# POWER.net
KiCad netlist of a schematic drawn in Altium Designer
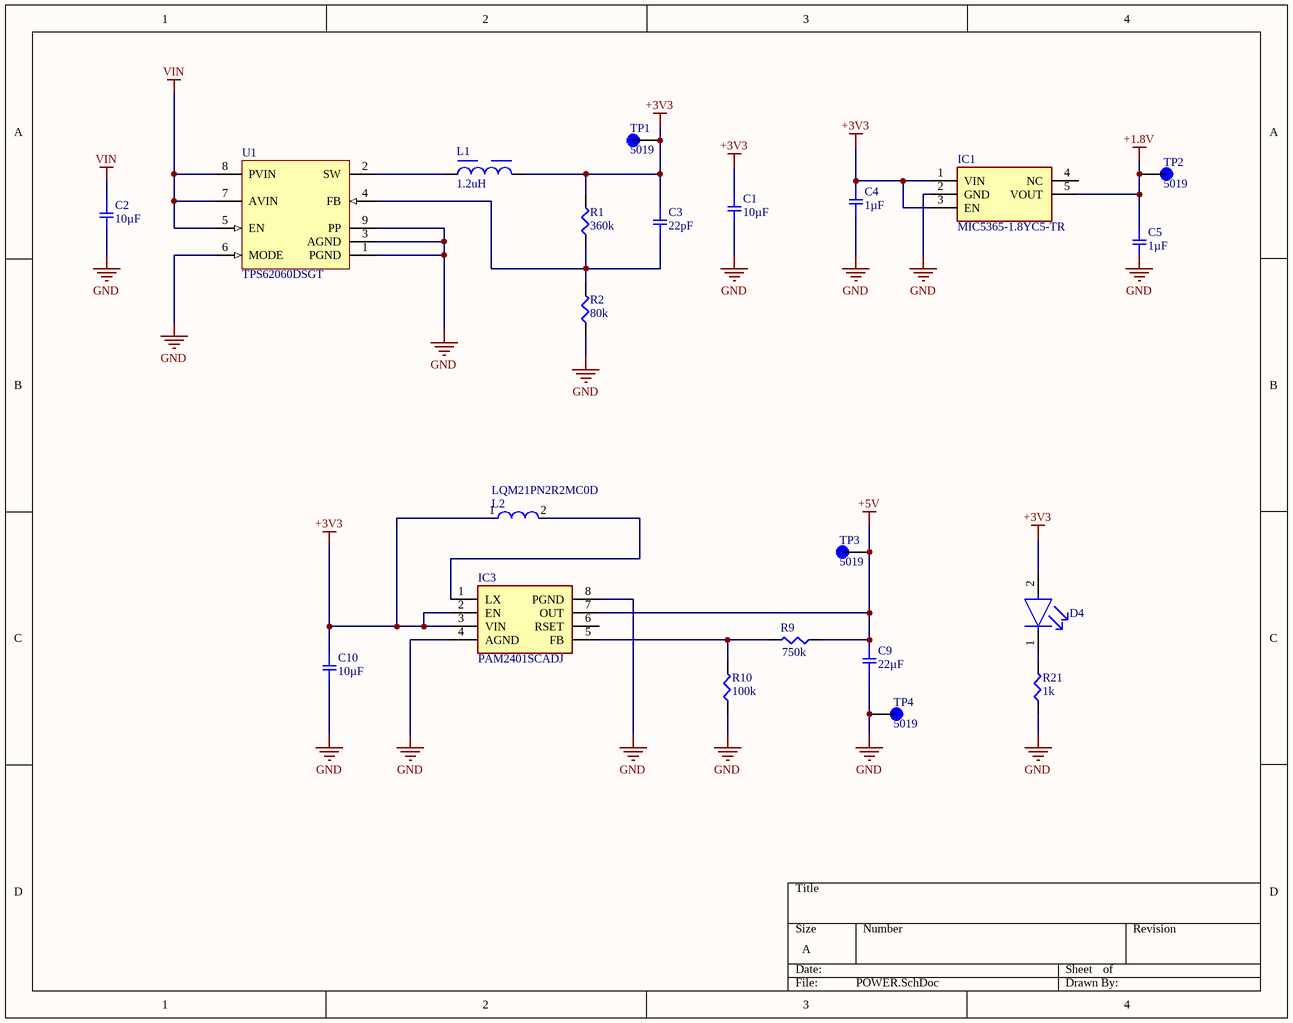
[diagram p0: POWER.SchDoc]

(export (version "E")
  (design (tool "Eeschema 10.0.6"))
  (components
    (comp (ref "C1")
      (value "10µF")
      (footprint "SMD-0603C")
      (description "CAP CER 10UF 16V X6S 0603")
      (fields
        (field (name "DIGI-KEY PART NUMBER") "490-7198-1-ND")
        (field (name "PART NUMBER") "GRM188C81C106MA73D")
      )
      (libsource (lib "capacitor_murata_0603") (part "GRM188C81C106MA73D"))
    )
    (comp (ref "C2")
      (value "10µF")
      (footprint "SMD-0603C")
      (description "CAP CER 10UF 16V X6S 0603")
      (fields
        (field (name "DIGI-KEY PART NUMBER") "490-7198-1-ND")
        (field (name "PART NUMBER") "GRM188C81C106MA73D")
      )
      (libsource (lib "capacitor_murata_0603") (part "GRM188C81C106MA73D"))
    )
    (comp (ref "C3")
      (value "22pF")
      (footprint "SMD-0402C")
      (description "CAP CER 22PF 50V NP0 0402")
      (fields
        (field (name "DIGI-KEY PART NUMBER") "490-9648-1-ND")
        (field (name "PART NUMBER") "GCM1555C1H220JA16D")
      )
      (libsource (lib "capacitor_murata_0402") (part "GCM1555C1H220JA16D"))
    )
    (comp (ref "C4")
      (value "1µF")
      (footprint "SMD-0402C")
      (description "CAP CER 1UF 10V X7S 0402")
      (fields
        (field (name "DIGI-KEY PART NUMBER") "490-13409-1-ND")
        (field (name "PART NUMBER") "GCM155C71A105KE38D")
      )
      (libsource (lib "capacitor_murata_0402") (part "GCM155C71A105KE38D"))
    )
    (comp (ref "C5")
      (value "1µF")
      (footprint "SMD-0402C")
      (description "CAP CER 1UF 10V X7S 0402")
      (fields
        (field (name "DIGI-KEY PART NUMBER") "490-13409-1-ND")
        (field (name "PART NUMBER") "GCM155C71A105KE38D")
      )
      (libsource (lib "capacitor_murata_0402") (part "GCM155C71A105KE38D"))
    )
    (comp (ref "C9")
      (value "22µF")
      (footprint "SMD-0603C")
      (description "CAP CER 22UF 6.3V X5S 0603")
      (fields
        (field (name "DIGI-KEY PART NUMBER") "490-10468-1-ND")
        (field (name "PART NUMBER") "GRM188C60J226MEA0D")
      )
      (libsource (lib "capacitor_murata_0603") (part "GRM188C60J226MEA0D"))
    )
    (comp (ref "C10")
      (value "10µF")
      (footprint "SMD-0603C")
      (description "CAP CER 10UF 16V X6S 0603")
      (fields
        (field (name "DIGI-KEY PART NUMBER") "490-7198-1-ND")
        (field (name "PART NUMBER") "GRM188C81C106MA73D")
      )
      (libsource (lib "capacitor_murata_0603") (part "GRM188C81C106MA73D"))
    )
    (comp (ref "D4")
      (value "APHHS1005CGCK")
      (footprint "FP-APHHS1005CGCK-MFG")
      (description "LED GREEN CLEAR CHIP SMD")
      (libsource (lib "Altium Content Vault") (part "8706943c75ba83719d021d2fdc84c58"))
    )
    (comp (ref "IC1")
      (value "MIC5365-1.8YC5-TR")
      (footprint "SamacSys:SOT65P210X110-5N")
      (description "Integrated Circuit")
      (fields (field (name "MOUSER PART NUMBER") "998-MIC5365-1.8YC5TR"))
      (libsource (lib "SamacSys") (part "MIC5365-1.8YC5-TR"))
    )
    (comp (ref "IC3")
      (value "PAM2401SCADJ")
      (footprint "SamacSys:SOP65P490X110-8N")
      (description "Integrated Circuit")
      (fields (field (name "MOUSER PART NUMBER") "621-PAM2401SCADJ"))
      (libsource (lib "*") (part "PAM2401SCADJ"))
    )
    (comp (ref "L1")
      (value "1.2uH")
      (footprint "WE-MAIA_1610")
      (description "78438313012 Power Inductor, Aec-Q200, 1.2Uh, 1.3A Rohs Compliant: Yes")
      (libsource (lib "Altium Content Vault") (part "Inductor - 3"))
    )
    (comp (ref "L2")
      (value "LQM21PN2R2MC0D")
      (footprint "FP-LQM21PN_C0-IPC_A")
      (description "Multilayer Type Inductor for Power Lines, 0805 (2012), 2.2μH, 20%, 0.425Ω, 0.6A")
      (fields (field (name "TOLERANCE") "20%"))
      (libsource (lib "Altium Content Vault") (part "725321dda6339637d4d059423bc1c3c"))
    )
    (comp (ref "R1")
      (value "360k")
      (footprint "SMD-0402-RES")
      (description "RES SMD 360K OHM 5% 1/10W 0402")
      (fields (field (name "PART NUMBER") "ERJ-2GEJ364X") (field (name "DIGI-KEY PART NUMBER") "P360KJCT-ND"))
      (libsource (lib "Panasonic_ERJ_0402") (part "ERJ-2GEJ364X"))
    )
    (comp (ref "R2")
      (value "80k")
      (footprint "SMD-0402-RES")
      (description "RES SMD 360K OHM 5% 1/10W 0402")
      (fields (field (name "PART NUMBER") "ERJ-2GEJ364X") (field (name "DIGI-KEY PART NUMBER") "P360KJCT-ND"))
      (libsource (lib "Panasonic_ERJ_0402") (part "ERJ-2GEJ364X"))
    )
    (comp (ref "R9")
      (value "750k")
      (footprint "SMD-0402-RES")
      (description "RES SMD 750K OHM 1% 1/10W 0402")
      (fields
        (field (name "PART NUMBER") "ERJ-2RKF7503X")
        (field (name "DIGI-KEY PART NUMBER") "P750KLCT-ND")
      )
      (libsource (lib "Panasonic_ERJ_0402") (part "ERJ-2RKF7503X"))
    )
    (comp (ref "R10")
      (value "100k")
      (footprint "SMD-0402-RES")
      (description "RES SMD 100K OHM 5% 1/10W 0402")
      (fields (field (name "PART NUMBER") "ERJ-2GEJ104X") (field (name "DIGI-KEY PART NUMBER") "P100KJCT-ND"))
      (libsource (lib "Panasonic_ERJ_0402") (part "ERJ-2GEJ104X"))
    )
    (comp (ref "R21")
      (value "1k")
      (footprint "SMD-0402-RES")
      (description "RES SMD 1K OHM 5% 1/10W 0402")
      (fields (field (name "PART NUMBER") "ERJ-2GEJ102X") (field (name "DIGI-KEY PART NUMBER") "P1.0KJCT-ND"))
      (libsource (lib "Panasonic_ERJ_0402") (part "ERJ-2GEJ102X"))
    )
    (comp (ref "TP1")
      (value "5019")
      (footprint "KEYSTONE_5019")
      (description "SMT Test Point- Mininature-1000 pc Reels")
      (fields (field (name "MF") "Keystone Electronics"))
      (libsource (lib "25)") (part "5019"))
    )
    (comp (ref "TP2")
      (value "5019")
      (footprint "KEYSTONE_5019")
      (description "SMT Test Point- Mininature-1000 pc Reels")
      (fields (field (name "MF") "Keystone Electronics"))
      (libsource (lib "25)") (part "5019"))
    )
    (comp (ref "TP3")
      (value "5019")
      (footprint "KEYSTONE_5019")
      (description "SMT Test Point- Mininature-1000 pc Reels")
      (fields (field (name "MF") "Keystone Electronics"))
      (libsource (lib "25)") (part "5019"))
    )
    (comp (ref "TP4")
      (value "5019")
      (footprint "KEYSTONE_5019")
      (description "SMT Test Point- Mininature-1000 pc Reels")
      (fields (field (name "MF") "Keystone Electronics"))
      (libsource (lib "25)") (part "5019"))
    )
    (comp (ref "U1")
      (value "TPS62060DSGT")
      (footprint "DSG0008A_V")
      (fields (field (name "MANUFACTURER") "Texas Instruments"))
      (libsource (lib "Altium Content Vault") (part "TI-TPS62060DSG8-1600X900TP"))
    )
  )
  (nets
    (net (code "1") (name "+1.8V") (class "Default")
      (node (ref "C5") (pin "1") (pinfunction "1_1") (pintype "passive"))
      (node (ref "IC1") (pin "5") (pinfunction "VOUT_5") (pintype "passive"))
      (node (ref "TP2") (pin "TP") (pinfunction "TP_TP") (pintype "passive"))
    )
    (net (code "2") (name "+3V3") (class "Default")
      (node (ref "C1") (pin "1") (pinfunction "1_1") (pintype "passive"))
      (node (ref "C10") (pin "1") (pinfunction "1_1") (pintype "passive"))
      (node (ref "C3") (pin "1") (pinfunction "1_1") (pintype "passive"))
      (node (ref "C4") (pin "1") (pinfunction "1_1") (pintype "passive"))
      (node (ref "D4") (pin "2") (pinfunction "A_2") (pintype "passive"))
      (node (ref "IC1") (pin "1") (pinfunction "VIN_1") (pintype "passive"))
      (node (ref "IC1") (pin "3") (pinfunction "EN_3") (pintype "passive"))
      (node (ref "IC3") (pin "2") (pinfunction "EN_2") (pintype "passive"))
      (node (ref "IC3") (pin "3") (pinfunction "VIN_3") (pintype "passive"))
      (node (ref "L1") (pin "2") (pinfunction "2_2") (pintype "passive"))
      (node (ref "L2") (pin "1") (pinfunction "1_1") (pintype "passive"))
      (node (ref "R1") (pin "2") (pinfunction "2_2") (pintype "passive"))
      (node (ref "TP1") (pin "TP") (pinfunction "TP_TP") (pintype "passive"))
    )
    (net (code "3") (name "+5V") (class "Default")
      (node (ref "C9") (pin "1") (pinfunction "1_1") (pintype "passive"))
      (node (ref "IC3") (pin "7") (pinfunction "OUT_7") (pintype "passive"))
      (node (ref "R9") (pin "1") (pinfunction "1_1") (pintype "passive"))
      (node (ref "TP3") (pin "TP") (pinfunction "TP_TP") (pintype "passive"))
    )
    (net (code "4") (name "GND") (class "Default")
      (node (ref "C1") (pin "2") (pinfunction "2_2") (pintype "passive"))
      (node (ref "C10") (pin "2") (pinfunction "2_2") (pintype "passive"))
      (node (ref "C2") (pin "2") (pinfunction "2_2") (pintype "passive"))
      (node (ref "C4") (pin "2") (pinfunction "2_2") (pintype "passive"))
      (node (ref "C5") (pin "2") (pinfunction "2_2") (pintype "passive"))
      (node (ref "C9") (pin "2") (pinfunction "2_2") (pintype "passive"))
      (node (ref "IC1") (pin "2") (pinfunction "GND_2") (pintype "passive"))
      (node (ref "IC3") (pin "4") (pinfunction "AGND_4") (pintype "passive"))
      (node (ref "IC3") (pin "8") (pinfunction "PGND_8") (pintype "passive"))
      (node (ref "R10") (pin "1") (pinfunction "1_1") (pintype "passive"))
      (node (ref "R2") (pin "1") (pinfunction "1_1") (pintype "passive"))
      (node (ref "R21") (pin "1") (pinfunction "1_1") (pintype "passive"))
      (node (ref "TP4") (pin "TP") (pinfunction "TP_TP") (pintype "passive"))
      (node (ref "U1") (pin "1") (pinfunction "PGND_1") (pintype "power_in"))
      (node (ref "U1") (pin "3") (pinfunction "AGND_3") (pintype "power_in"))
      (node (ref "U1") (pin "6") (pinfunction "MODE_6") (pintype "input"))
      (node (ref "U1") (pin "9") (pinfunction "PP_9") (pintype "power_in"))
    )
    (net (code "5") (name "Net-(D4-C)") (class "Default")
      (node (ref "D4") (pin "1") (pinfunction "C_1") (pintype "passive"))
      (node (ref "R21") (pin "2") (pinfunction "2_2") (pintype "passive"))
    )
    (net (code "6") (name "Net-(IC3-FB)") (class "Default")
      (node (ref "IC3") (pin "5") (pinfunction "FB_5") (pintype "passive"))
      (node (ref "R10") (pin "2") (pinfunction "2_2") (pintype "passive"))
      (node (ref "R9") (pin "2") (pinfunction "2_2") (pintype "passive"))
    )
    (net (code "7") (name "Net-(IC3-LX)") (class "Default")
      (node (ref "IC3") (pin "1") (pinfunction "LX_1") (pintype "passive"))
      (node (ref "L2") (pin "2") (pinfunction "2_2") (pintype "passive"))
    )
    (net (code "8") (name "Net-(U1-FB)") (class "Default")
      (node (ref "C3") (pin "2") (pinfunction "2_2") (pintype "passive"))
      (node (ref "R1") (pin "1") (pinfunction "1_1") (pintype "passive"))
      (node (ref "R2") (pin "2") (pinfunction "2_2") (pintype "passive"))
      (node (ref "U1") (pin "4") (pinfunction "FB_4") (pintype "input"))
    )
    (net (code "9") (name "Net-(U1-SW)") (class "Default")
      (node (ref "L1") (pin "1") (pinfunction "1_1") (pintype "passive"))
      (node (ref "U1") (pin "2") (pinfunction "SW_2") (pintype "power_in"))
    )
    (net (code "10") (name "VIN") (class "Default")
      (node (ref "C2") (pin "1") (pinfunction "1_1") (pintype "passive"))
      (node (ref "U1") (pin "5") (pinfunction "EN_5") (pintype "input"))
      (node (ref "U1") (pin "7") (pinfunction "AVIN_7") (pintype "power_in"))
      (node (ref "U1") (pin "8") (pinfunction "PVIN_8") (pintype "power_in"))
    )
    (net (code "11") (name "unconnected-(IC1-NC-Pad4)") (class "Default")
      (node (ref "IC1") (pin "4") (pinfunction "NC_4") (pintype "passive"))
    )
    (net (code "12") (name "unconnected-(IC3-RSET-Pad6)") (class "Default")
      (node (ref "IC3") (pin "6") (pinfunction "RSET_6") (pintype "passive"))
    )
  )
)
